# tricorder-featherwing-mk-1_3.net
KiCad netlist of a schematic drawn in EAGLE
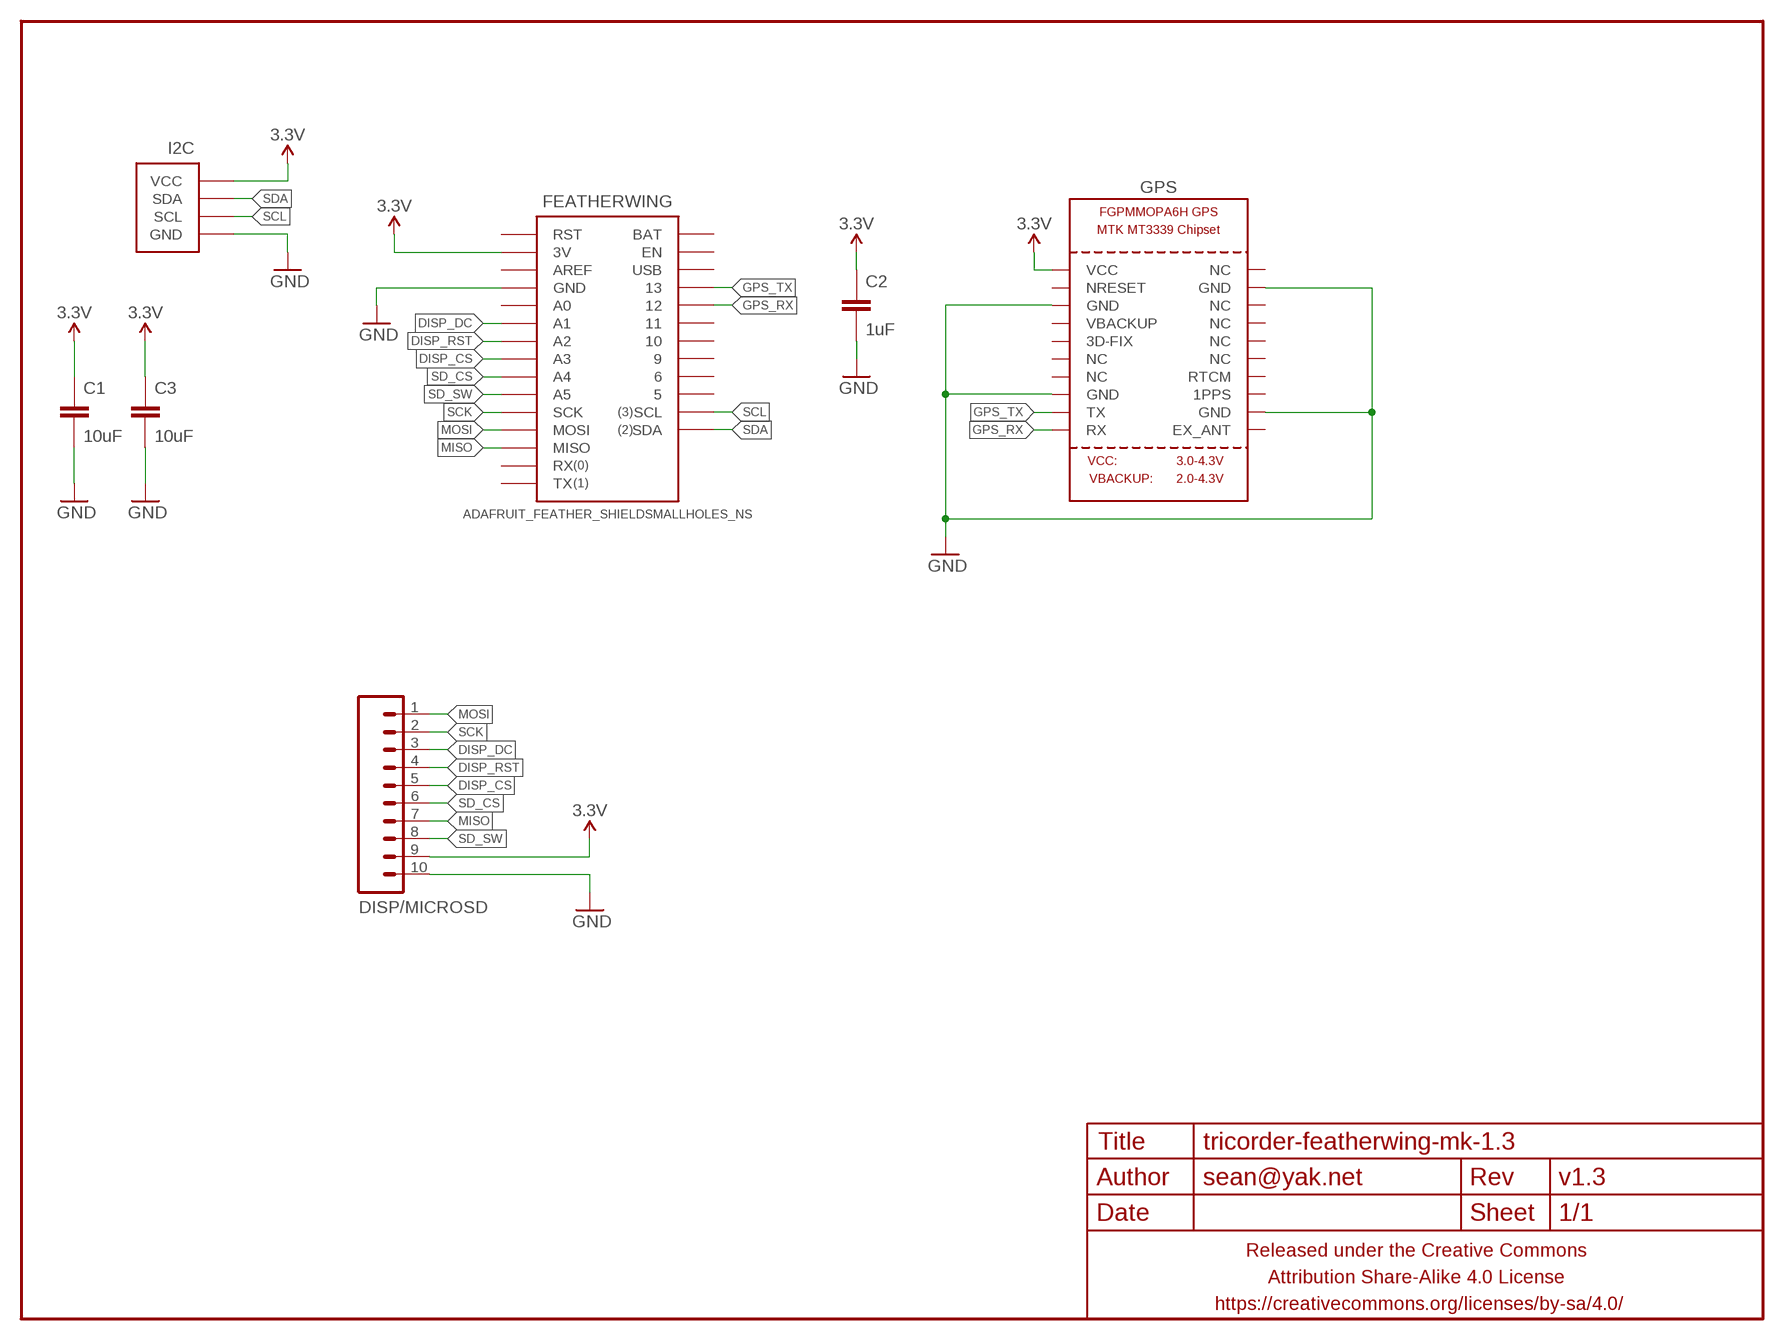
[diagram p0: schematic, sheet 1]

(export (version "E")
  (design (tool "Eeschema 10.0.6"))
  (components
    (comp (ref "C1")
      (value "10uF")
      (footprint "eagle-import:C1210")
      (libsource (lib "eagle-import") (part "CAPACITOR-CERAMICC1210"))
    )
    (comp (ref "C2")
      (value "1uF")
      (footprint "eagle-import:C0603")
      (libsource (lib "eagle-import") (part "CAPACITOR-CERAMICC0603"))
    )
    (comp (ref "C3")
      (value "10uF")
      (footprint "eagle-import:C1210")
      (libsource (lib "eagle-import") (part "CAPACITOR-CERAMICC1210"))
    )
    (comp (ref "DISP/MICROSD")
      (value "M10JST-10-PH-RA-PTH")
      (footprint "eagle-import:JST-10-PH-RA-PTH")
      (libsource (lib "eagle-import") (part "M10JST-10-PH-RA-PTH"))
    )
    (comp (ref "FEATHERWING")
      (value "ADAFRUIT_FEATHER_SHIELDSMALLHOLES_NS")
      (footprint "eagle-import:ADAFRUIT_FEATHER_SMALLHOLES_NS")
      (libsource (lib "eagle-import") (part "ADAFRUIT_FEATHER_SHIELDSMALLHOLES_NS"))
    )
    (comp (ref "FRAME1")
      (value "FRAME-LETTERNO_PACKAGE")
      (footprint "eagle-import:DUMMY")
      (fields (field (name "DESIGNER") "sean@yak.net") (field (name "VERSION") "v1.3"))
      (libsource (lib "eagle-import") (part "FRAME-LETTERNO_PACKAGE"))
    )
    (comp (ref "GPS")
      (value "GPS_FGPMMOPA6H")
      (footprint "eagle-import:FGPMMOPA6H")
      (libsource (lib "eagle-import") (part "GPS_FGPMMOPA6H"))
    )
    (comp (ref "I2C")
      (value "M04-I2CPTH-0.1IN-CENTERED")
      (footprint "eagle-import:1X04-PTH-VERT-I2C-CENTERED")
      (libsource (lib "eagle-import") (part "M04-I2CPTH-0.1IN-CENTERED"))
    )
  )
  (nets
    (net (code "1") (name "3.3V") (class "Default")
      (node (ref "C1") (pin "1") (pinfunction "1_1") (pintype "passive"))
      (node (ref "C2") (pin "1") (pinfunction "1_1") (pintype "passive"))
      (node (ref "C3") (pin "1") (pinfunction "1_1") (pintype "passive"))
      (node (ref "DISP/MICROSD") (pin "9") (pinfunction "9_9") (pintype "passive"))
      (node (ref "FEATHERWING") (pin "3V") (pinfunction "3V_3V") (pintype "bidirectional"))
      (node (ref "GPS") (pin "P$1") (pinfunction "VCC_P$1") (pintype "bidirectional"))
      (node (ref "I2C") (pin "VCC") (pinfunction "VCC_VCC") (pintype "bidirectional"))
    )
    (net (code "2") (name "DISP_CS") (class "Default")
      (node (ref "DISP/MICROSD") (pin "5") (pinfunction "5_5") (pintype "passive"))
      (node (ref "FEATHERWING") (pin "A3") (pinfunction "A3_A3") (pintype "bidirectional"))
    )
    (net (code "3") (name "DISP_DC") (class "Default")
      (node (ref "DISP/MICROSD") (pin "3") (pinfunction "3_3") (pintype "passive"))
      (node (ref "FEATHERWING") (pin "A1") (pinfunction "A1_A1") (pintype "bidirectional"))
    )
    (net (code "4") (name "DISP_RST") (class "Default")
      (node (ref "DISP/MICROSD") (pin "4") (pinfunction "4_4") (pintype "passive"))
      (node (ref "FEATHERWING") (pin "A2") (pinfunction "A2_A2") (pintype "bidirectional"))
    )
    (net (code "5") (name "GND") (class "Default")
      (node (ref "C1") (pin "2") (pinfunction "2_2") (pintype "passive"))
      (node (ref "C2") (pin "2") (pinfunction "2_2") (pintype "passive"))
      (node (ref "C3") (pin "2") (pinfunction "2_2") (pintype "passive"))
      (node (ref "DISP/MICROSD") (pin "10") (pinfunction "10_10") (pintype "passive"))
      (node (ref "FEATHERWING") (pin "GND@0") (pinfunction "GND_GND@0") (pintype "bidirectional"))
      (node (ref "FEATHERWING") (pin "GND@1") (pinfunction "GND_GND@1") (pintype "bidirectional"))
      (node (ref "GPS") (pin "P$12") (pinfunction "GND_P$12") (pintype "bidirectional"))
      (node (ref "GPS") (pin "P$19") (pinfunction "GND_P$19") (pintype "bidirectional"))
      (node (ref "GPS") (pin "P$3") (pinfunction "GND_P$3") (pintype "bidirectional"))
      (node (ref "GPS") (pin "P$8") (pinfunction "GND_P$8") (pintype "bidirectional"))
      (node (ref "I2C") (pin "GND") (pinfunction "GND_GND") (pintype "bidirectional"))
    )
    (net (code "6") (name "GPS_RX") (class "Default")
      (node (ref "FEATHERWING") (pin "12") (pinfunction "12_12") (pintype "bidirectional"))
      (node (ref "GPS") (pin "P$10") (pinfunction "RX_P$10") (pintype "bidirectional"))
    )
    (net (code "7") (name "GPS_TX") (class "Default")
      (node (ref "FEATHERWING") (pin "13") (pinfunction "13_13") (pintype "bidirectional"))
      (node (ref "GPS") (pin "P$9") (pinfunction "TX_P$9") (pintype "bidirectional"))
    )
    (net (code "8") (name "MISO") (class "Default")
      (node (ref "DISP/MICROSD") (pin "7") (pinfunction "7_7") (pintype "passive"))
      (node (ref "FEATHERWING") (pin "MISO") (pinfunction "MISO_MISO") (pintype "bidirectional"))
    )
    (net (code "9") (name "MOSI") (class "Default")
      (node (ref "DISP/MICROSD") (pin "1") (pinfunction "1_1") (pintype "passive"))
      (node (ref "FEATHERWING") (pin "MOSI") (pinfunction "MOSI_MOSI") (pintype "bidirectional"))
    )
    (net (code "10") (name "SCK") (class "Default")
      (node (ref "DISP/MICROSD") (pin "2") (pinfunction "2_2") (pintype "passive"))
      (node (ref "FEATHERWING") (pin "SCK") (pinfunction "SCK_SCK") (pintype "bidirectional"))
    )
    (net (code "11") (name "SCL") (class "Default")
      (node (ref "FEATHERWING") (pin "SCL") (pinfunction "SCL_SCL") (pintype "bidirectional"))
      (node (ref "I2C") (pin "SCL") (pinfunction "SCL_SCL") (pintype "bidirectional"))
    )
    (net (code "12") (name "SDA") (class "Default")
      (node (ref "FEATHERWING") (pin "SDA") (pinfunction "SDA_SDA") (pintype "bidirectional"))
      (node (ref "I2C") (pin "SDA") (pinfunction "SDA_SDA") (pintype "bidirectional"))
    )
    (net (code "13") (name "SD_CS") (class "Default")
      (node (ref "DISP/MICROSD") (pin "6") (pinfunction "6_6") (pintype "passive"))
      (node (ref "FEATHERWING") (pin "A4") (pinfunction "A4_A4") (pintype "bidirectional"))
    )
    (net (code "14") (name "SD_SW") (class "Default")
      (node (ref "DISP/MICROSD") (pin "8") (pinfunction "8_8") (pintype "passive"))
      (node (ref "FEATHERWING") (pin "A5") (pinfunction "A5_A5") (pintype "bidirectional"))
    )
    (net (code "15") (name "unconnected-(FEATHERWING-Pad5)") (class "Default")
      (node (ref "FEATHERWING") (pin "5") (pinfunction "5_5") (pintype "bidirectional"))
    )
    (net (code "16") (name "unconnected-(FEATHERWING-Pad6)") (class "Default")
      (node (ref "FEATHERWING") (pin "6") (pinfunction "6_6") (pintype "bidirectional"))
    )
    (net (code "17") (name "unconnected-(FEATHERWING-Pad9)") (class "Default")
      (node (ref "FEATHERWING") (pin "9") (pinfunction "9_9") (pintype "bidirectional"))
    )
    (net (code "18") (name "unconnected-(FEATHERWING-Pad10)") (class "Default")
      (node (ref "FEATHERWING") (pin "10") (pinfunction "10_10") (pintype "bidirectional"))
    )
    (net (code "19") (name "unconnected-(FEATHERWING-Pad11)") (class "Default")
      (node (ref "FEATHERWING") (pin "11") (pinfunction "11_11") (pintype "bidirectional"))
    )
    (net (code "20") (name "unconnected-(FEATHERWING-PadA0)") (class "Default")
      (node (ref "FEATHERWING") (pin "A0") (pinfunction "A0_A0") (pintype "bidirectional"))
    )
    (net (code "21") (name "unconnected-(FEATHERWING-PadAREF)") (class "Default")
      (node (ref "FEATHERWING") (pin "AREF") (pinfunction "AREF_AREF") (pintype "bidirectional"))
    )
    (net (code "22") (name "unconnected-(FEATHERWING-PadBAT)") (class "Default")
      (node (ref "FEATHERWING") (pin "BAT") (pinfunction "BAT_BAT") (pintype "bidirectional"))
    )
    (net (code "23") (name "unconnected-(FEATHERWING-PadEN)") (class "Default")
      (node (ref "FEATHERWING") (pin "EN") (pinfunction "EN_EN") (pintype "bidirectional"))
    )
    (net (code "24") (name "unconnected-(FEATHERWING-PadRST)") (class "Default")
      (node (ref "FEATHERWING") (pin "RST") (pinfunction "RST_RST") (pintype "bidirectional"))
    )
    (net (code "25") (name "unconnected-(FEATHERWING-PadRX)") (class "Default")
      (node (ref "FEATHERWING") (pin "RX") (pinfunction "RX_RX") (pintype "bidirectional"))
    )
    (net (code "26") (name "unconnected-(FEATHERWING-PadTX)") (class "Default")
      (node (ref "FEATHERWING") (pin "TX") (pinfunction "TX_TX") (pintype "bidirectional"))
    )
    (net (code "27") (name "unconnected-(FEATHERWING-PadUSB)") (class "Default")
      (node (ref "FEATHERWING") (pin "USB") (pinfunction "USB_USB") (pintype "bidirectional"))
    )
    (net (code "28") (name "unconnected-(GPS-1PPS-PadP$13)") (class "Default")
      (node (ref "GPS") (pin "P$13") (pinfunction "1PPS_P$13") (pintype "bidirectional"))
    )
    (net (code "29") (name "unconnected-(GPS-3D-FIX-PadP$5)") (class "Default")
      (node (ref "GPS") (pin "P$5") (pinfunction "3D-FIX_P$5") (pintype "bidirectional"))
    )
    (net (code "30") (name "unconnected-(GPS-EX_ANT-PadP$11)") (class "Default")
      (node (ref "GPS") (pin "P$11") (pinfunction "EX_ANT_P$11") (pintype "bidirectional"))
    )
    (net (code "31") (name "unconnected-(GPS-NC-PadP$6)") (class "Default")
      (node (ref "GPS") (pin "P$6") (pinfunction "NC_P$6") (pintype "bidirectional"))
    )
    (net (code "32") (name "unconnected-(GPS-NC-PadP$7)") (class "Default")
      (node (ref "GPS") (pin "P$7") (pinfunction "NC_P$7") (pintype "bidirectional"))
    )
    (net (code "33") (name "unconnected-(GPS-NC-PadP$15)") (class "Default")
      (node (ref "GPS") (pin "P$15") (pinfunction "NC_P$15") (pintype "bidirectional"))
    )
    (net (code "34") (name "unconnected-(GPS-NC-PadP$16)") (class "Default")
      (node (ref "GPS") (pin "P$16") (pinfunction "NC_P$16") (pintype "bidirectional"))
    )
    (net (code "35") (name "unconnected-(GPS-NC-PadP$17)") (class "Default")
      (node (ref "GPS") (pin "P$17") (pinfunction "NC_P$17") (pintype "bidirectional"))
    )
    (net (code "36") (name "unconnected-(GPS-NC-PadP$18)") (class "Default")
      (node (ref "GPS") (pin "P$18") (pinfunction "NC_P$18") (pintype "bidirectional"))
    )
    (net (code "37") (name "unconnected-(GPS-NC-PadP$20)") (class "Default")
      (node (ref "GPS") (pin "P$20") (pinfunction "NC_P$20") (pintype "bidirectional"))
    )
    (net (code "38") (name "unconnected-(GPS-NRESET-PadP$2)") (class "Default")
      (node (ref "GPS") (pin "P$2") (pinfunction "NRESET_P$2") (pintype "bidirectional"))
    )
    (net (code "39") (name "unconnected-(GPS-RTCM-PadP$14)") (class "Default")
      (node (ref "GPS") (pin "P$14") (pinfunction "RTCM_P$14") (pintype "bidirectional"))
    )
    (net (code "40") (name "unconnected-(GPS-VBACKUP-PadP$4)") (class "Default")
      (node (ref "GPS") (pin "P$4") (pinfunction "VBACKUP_P$4") (pintype "bidirectional"))
    )
  )
)
